# shangchi.net
KiCad netlist of a schematic drawn in EasyEDA Pro
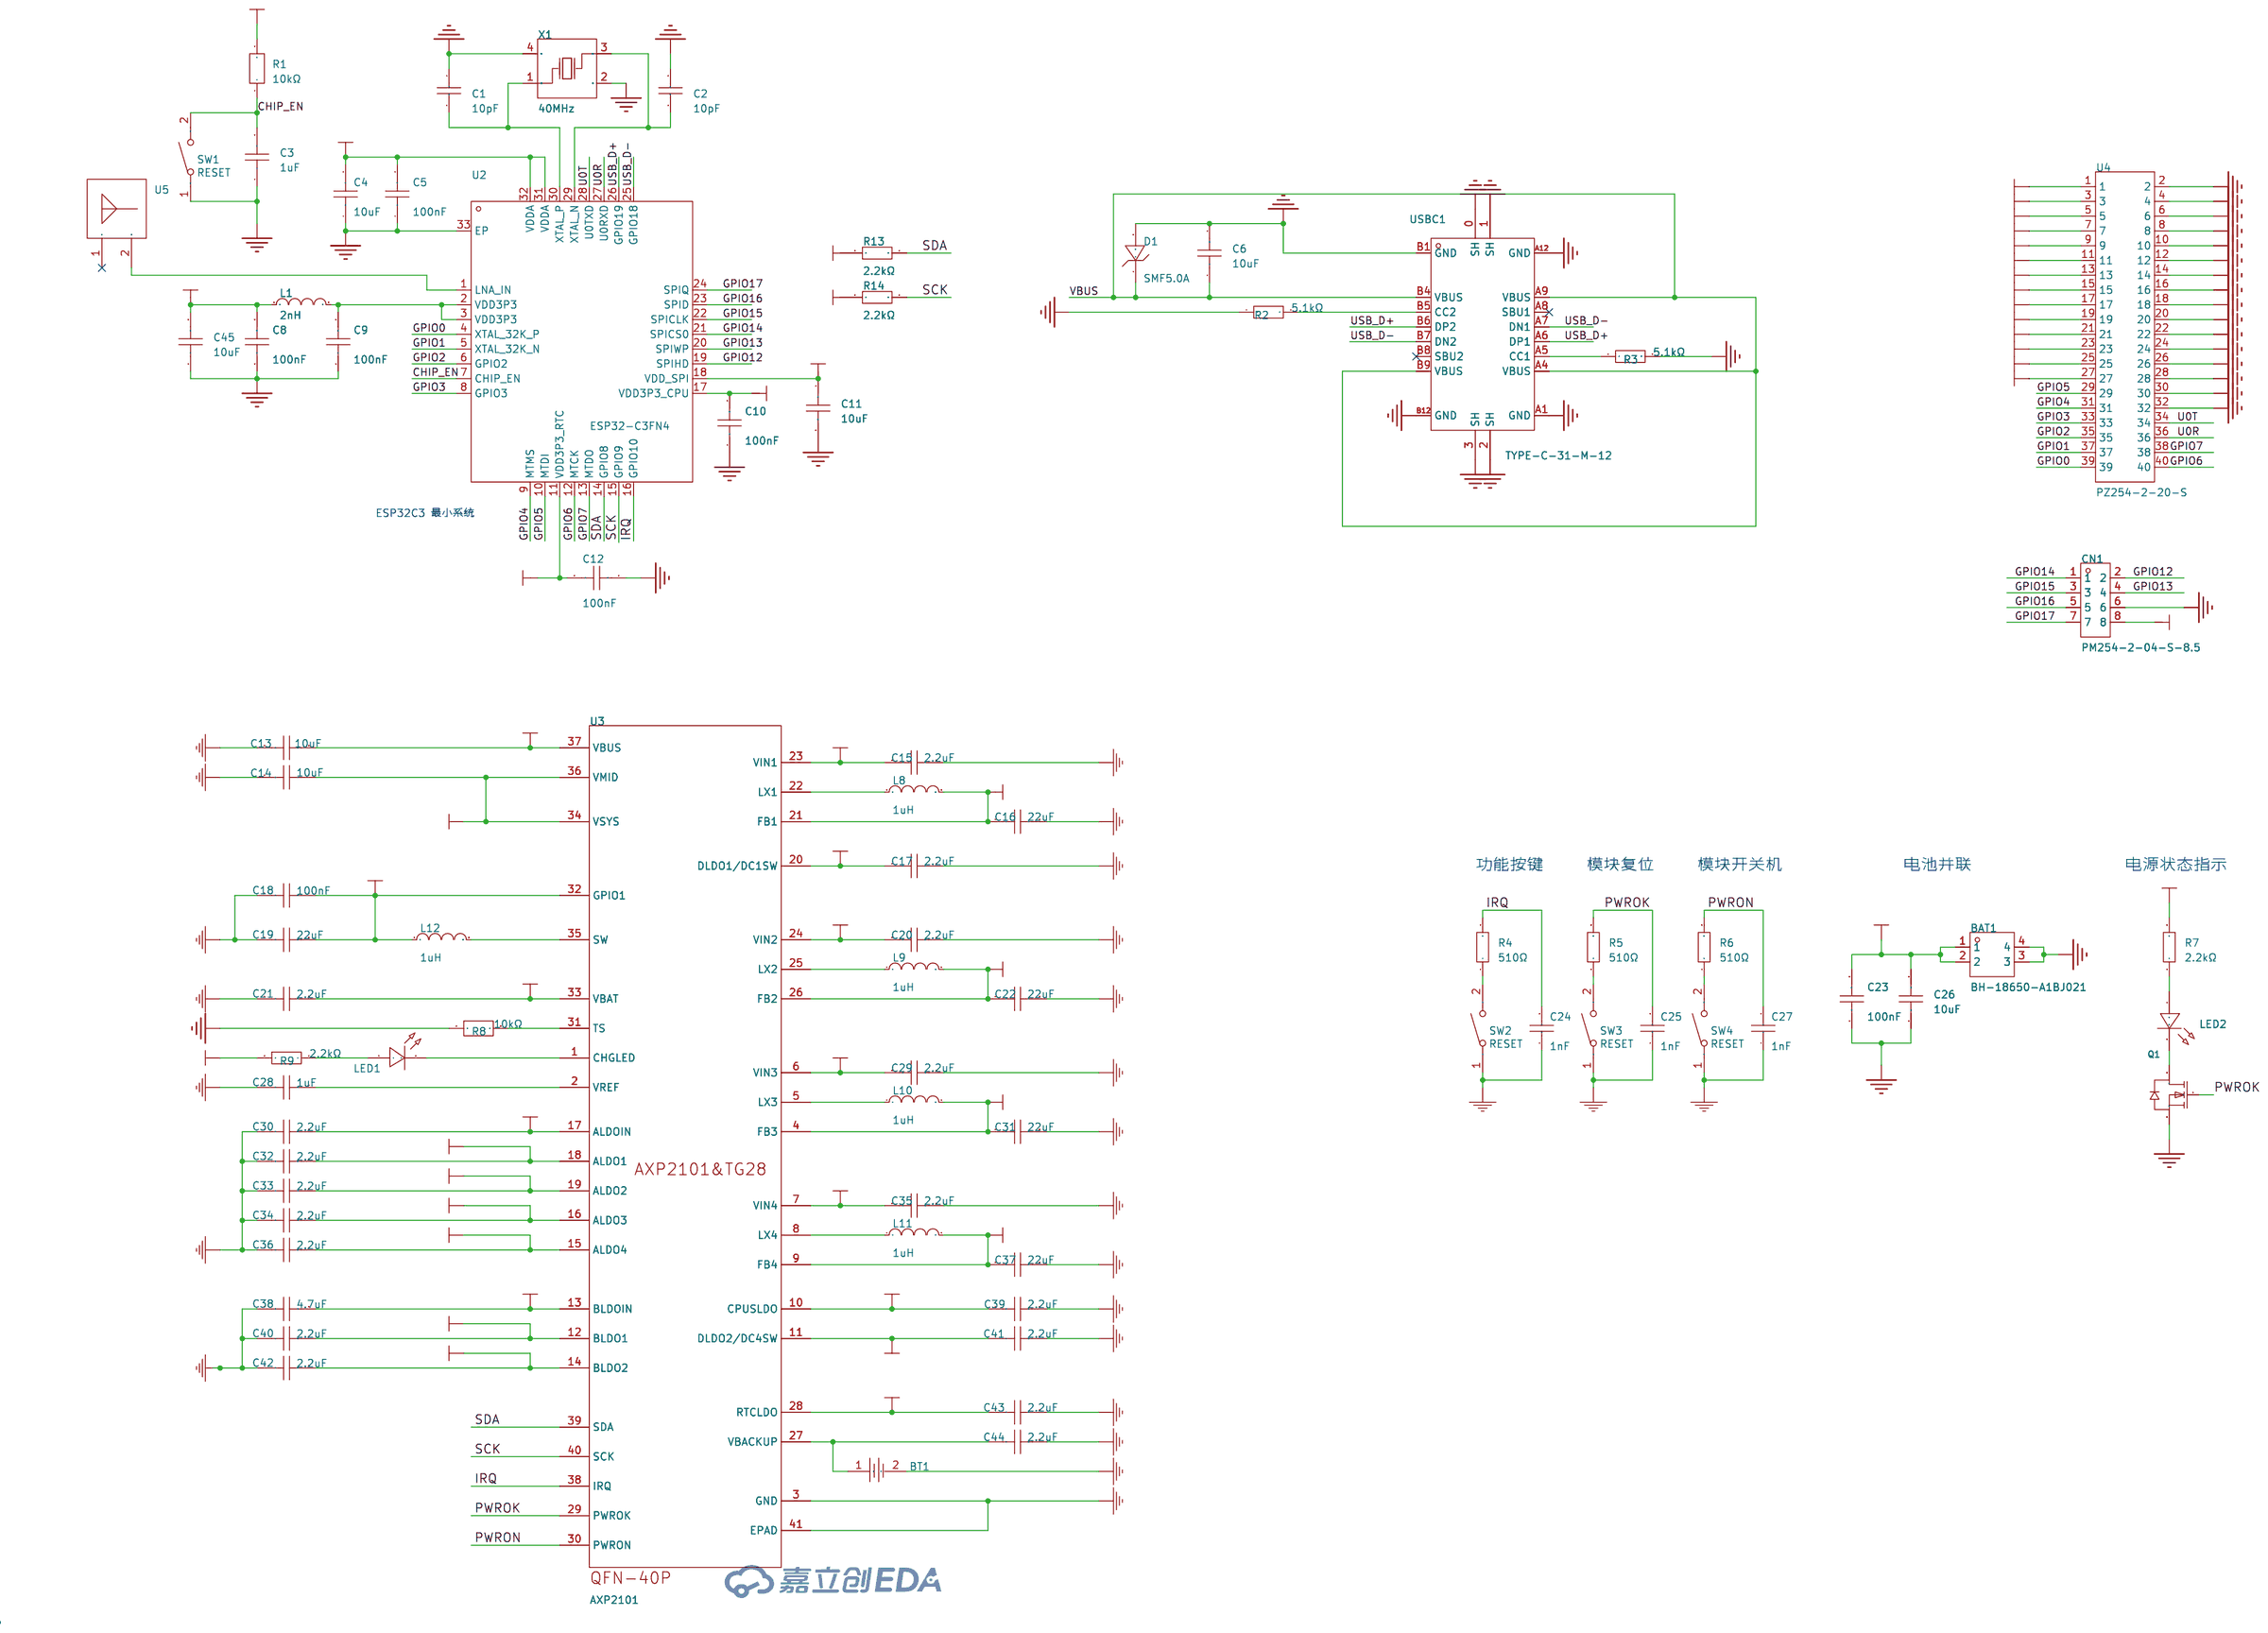
[diagram p0: schematic sheet]

(export (version "E")
  (design (tool "Eeschema 10.0.6"))
  (components
    (comp (ref "BAT1")
      (value "BH-18650-A1BJ021")
      (footprint "easyedapro:BAT-TH_L77.0-W39.9_BH-18650-A1BJ021")
      (description "连接器类型:电池盒;适用电池规格:-;触点电镀:镍;工作温度范围:-25°C~+85°C;")
      (fields (field (name "Manufacturer") "MYOUNG(美阳)"))
      (libsource (lib "easyedapro") (part "BH-18650-A1BJ021"))
    )
    (comp (ref "BT1")
      (value "CR1220-2ZX")
      (footprint "easyedapro:BAT-SMD_CR1220-2ZX")
      (fields (field (name "Manufacturer") "Q&J"))
      (libsource (lib "easyedapro") (part "CR1220-2ZX"))
    )
    (comp (ref "C1")
      (value "10pF")
      (footprint "easyedapro:C0603")
      (description "容值:10pF;精度:±5%;额定电压:50V;材质(温度系数):C0G;")
      (fields
        (field (name "Manufacturer Part") "CL10C100JB8NNNC")
        (field (name "Manufacturer") "SAMSUNG(三星)")
      )
      (libsource (lib "easyedapro") (part "CL10C100JB8NNNC"))
    )
    (comp (ref "C2")
      (value "10pF")
      (footprint "easyedapro:C0603")
      (description "容值:10pF;精度:±5%;额定电压:50V;材质(温度系数):C0G;")
      (fields
        (field (name "Manufacturer Part") "CL10C100JB8NNNC")
        (field (name "Manufacturer") "SAMSUNG(三星)")
      )
      (libsource (lib "easyedapro") (part "CL10C100JB8NNNC"))
    )
    (comp (ref "C3")
      (value "1uF")
      (fields (field (name "Manufacturer") "SAMSUNG(三星)"))
      (libsource (lib "easyedapro") (part "1uF/0603"))
    )
    (comp (ref "C4")
      (value "10uF")
      (footprint "easyedapro:C0603")
      (description "容值:10uF;精度:±10%;额定电压:10V;材质(温度系数):X5R;")
      (fields
        (field (name "Manufacturer Part") "CL10A106KP8NNNC")
        (field (name "Manufacturer") "SAMSUNG(三星)")
      )
      (libsource (lib "easyedapro") (part "CL10A106KP8NNNC"))
    )
    (comp (ref "C5")
      (value "100nF")
      (fields (field (name "Manufacturer") "SAMSUNG(三星)"))
      (libsource (lib "easyedapro") (part "100nF/0603"))
    )
    (comp (ref "C6")
      (value "10uF")
      (footprint "easyedapro:C0603")
      (description "容值:10uF;精度:±10%;额定电压:10V;材质(温度系数):X5R;")
      (fields
        (field (name "Manufacturer Part") "CL10A106KP8NNNC")
        (field (name "Manufacturer") "SAMSUNG(三星)")
      )
      (libsource (lib "easyedapro") (part "CL10A106KP8NNNC"))
    )
    (comp (ref "C8")
      (value "100nF")
      (fields (field (name "Manufacturer") "SAMSUNG(三星)"))
      (libsource (lib "easyedapro") (part "100nF/0603"))
    )
    (comp (ref "C9")
      (value "100nF")
      (fields (field (name "Manufacturer") "SAMSUNG(三星)"))
      (libsource (lib "easyedapro") (part "100nF/0603"))
    )
    (comp (ref "C10")
      (value "100nF")
      (fields (field (name "Manufacturer") "SAMSUNG(三星)"))
      (libsource (lib "easyedapro") (part "100nF/0603"))
    )
    (comp (ref "C11")
      (value "10uF")
      (fields (field (name "Manufacturer") "SAMSUNG(三星)"))
      (libsource (lib "easyedapro") (part "10uF/0603"))
    )
    (comp (ref "C12")
      (value "100nF")
      (fields (field (name "Manufacturer") "SAMSUNG(三星)"))
      (libsource (lib "easyedapro") (part "100nF/0603"))
    )
    (comp (ref "C13")
      (value "10uF")
      (footprint "easyedapro:C0603")
      (description "容值:10uF;精度:±10%;额定电压:10V;材质(温度系数):X5R;")
      (fields
        (field (name "Manufacturer Part") "CL10A106KP8NNNC")
        (field (name "Manufacturer") "SAMSUNG(三星)")
      )
      (libsource (lib "easyedapro") (part "CL10A106KP8NNNC"))
    )
    (comp (ref "C14")
      (value "10uF")
      (fields (field (name "Manufacturer") "SAMSUNG(三星)"))
      (libsource (lib "easyedapro") (part "10uF/0603"))
    )
    (comp (ref "C15")
      (value "2.2uF")
      (fields (field (name "Manufacturer") "SAMSUNG(三星)"))
      (libsource (lib "easyedapro") (part "2.2uF/0603"))
    )
    (comp (ref "C16")
      (value "22uF")
      (fields (field (name "Manufacturer") "SAMSUNG(三星)"))
      (libsource (lib "easyedapro") (part "22uF/0603"))
    )
    (comp (ref "C17")
      (value "2.2uF")
      (fields (field (name "Manufacturer") "SAMSUNG(三星)"))
      (libsource (lib "easyedapro") (part "2.2uF/0603"))
    )
    (comp (ref "C18")
      (value "100nF")
      (fields (field (name "Manufacturer") "SAMSUNG(三星)"))
      (libsource (lib "easyedapro") (part "100nF/0603"))
    )
    (comp (ref "C19")
      (value "22uF")
      (fields (field (name "Manufacturer") "SAMSUNG(三星)"))
      (libsource (lib "easyedapro") (part "22uF/0603"))
    )
    (comp (ref "C20")
      (value "2.2uF")
      (fields (field (name "Manufacturer") "SAMSUNG(三星)"))
      (libsource (lib "easyedapro") (part "2.2uF/0603"))
    )
    (comp (ref "C21")
      (value "2.2uF")
      (fields (field (name "Manufacturer") "SAMSUNG(三星)"))
      (libsource (lib "easyedapro") (part "2.2uF/0603"))
    )
    (comp (ref "C22")
      (value "22uF")
      (fields (field (name "Manufacturer") "SAMSUNG(三星)"))
      (libsource (lib "easyedapro") (part "22uF/0603"))
    )
    (comp (ref "C23")
      (value "100nF")
      (fields (field (name "Manufacturer") "SAMSUNG(三星)"))
      (libsource (lib "easyedapro") (part "100nF/0603"))
    )
    (comp (ref "C24")
      (value "1nF")
      (footprint "easyedapro:C0603")
      (description "容值:1nF;精度:±10%;额定电压:50V;材质(温度系数):X7R;")
      (fields
        (field (name "Manufacturer Part") "CL10B102KB8NNNC")
        (field (name "Manufacturer") "SAMSUNG(三星)")
      )
      (libsource (lib "easyedapro") (part "CL10B102KB8NNNC"))
    )
    (comp (ref "C25")
      (value "1nF")
      (footprint "easyedapro:C0603")
      (description "容值:1nF;精度:±10%;额定电压:50V;材质(温度系数):X7R;")
      (fields
        (field (name "Manufacturer Part") "CL10B102KB8NNNC")
        (field (name "Manufacturer") "SAMSUNG(三星)")
      )
      (libsource (lib "easyedapro") (part "CL10B102KB8NNNC"))
    )
    (comp (ref "C26")
      (value "10uF")
      (footprint "easyedapro:C0603")
      (description "容值:10uF;精度:±10%;额定电压:10V;材质(温度系数):X5R;")
      (fields
        (field (name "Manufacturer Part") "CL10A106KP8NNNC")
        (field (name "Manufacturer") "SAMSUNG(三星)")
      )
      (libsource (lib "easyedapro") (part "CL10A106KP8NNNC"))
    )
    (comp (ref "C27")
      (value "1nF")
      (footprint "easyedapro:C0603")
      (description "容值:1nF;精度:±10%;额定电压:50V;材质(温度系数):X7R;")
      (fields
        (field (name "Manufacturer Part") "CL10B102KB8NNNC")
        (field (name "Manufacturer") "SAMSUNG(三星)")
      )
      (libsource (lib "easyedapro") (part "CL10B102KB8NNNC"))
    )
    (comp (ref "C28")
      (value "1uF")
      (fields (field (name "Manufacturer") "SAMSUNG(三星)"))
      (libsource (lib "easyedapro") (part "1uF/0603"))
    )
    (comp (ref "C29")
      (value "2.2uF")
      (fields (field (name "Manufacturer") "SAMSUNG(三星)"))
      (libsource (lib "easyedapro") (part "2.2uF/0603"))
    )
    (comp (ref "C30")
      (value "2.2uF")
      (fields (field (name "Manufacturer") "SAMSUNG(三星)"))
      (libsource (lib "easyedapro") (part "2.2uF/0603"))
    )
    (comp (ref "C31")
      (value "22uF")
      (fields (field (name "Manufacturer") "SAMSUNG(三星)"))
      (libsource (lib "easyedapro") (part "22uF/0603"))
    )
    (comp (ref "C32")
      (value "2.2uF")
      (fields (field (name "Manufacturer") "SAMSUNG(三星)"))
      (libsource (lib "easyedapro") (part "2.2uF/0603"))
    )
    (comp (ref "C33")
      (value "2.2uF")
      (fields (field (name "Manufacturer") "SAMSUNG(三星)"))
      (libsource (lib "easyedapro") (part "2.2uF/0603"))
    )
    (comp (ref "C34")
      (value "2.2uF")
      (fields (field (name "Manufacturer") "SAMSUNG(三星)"))
      (libsource (lib "easyedapro") (part "2.2uF/0603"))
    )
    (comp (ref "C35")
      (value "2.2uF")
      (fields (field (name "Manufacturer") "SAMSUNG(三星)"))
      (libsource (lib "easyedapro") (part "2.2uF/0603"))
    )
    (comp (ref "C36")
      (value "2.2uF")
      (fields (field (name "Manufacturer") "SAMSUNG(三星)"))
      (libsource (lib "easyedapro") (part "2.2uF/0603"))
    )
    (comp (ref "C37")
      (value "22uF")
      (fields (field (name "Manufacturer") "SAMSUNG(三星)"))
      (libsource (lib "easyedapro") (part "22uF/0603"))
    )
    (comp (ref "C38")
      (value "4.7uF")
      (fields (field (name "Manufacturer") "SAMSUNG(三星)"))
      (libsource (lib "easyedapro") (part "4.7uF/0603"))
    )
    (comp (ref "C39")
      (value "2.2uF")
      (fields (field (name "Manufacturer") "SAMSUNG(三星)"))
      (libsource (lib "easyedapro") (part "2.2uF/0603"))
    )
    (comp (ref "C40")
      (value "2.2uF")
      (fields (field (name "Manufacturer") "SAMSUNG(三星)"))
      (libsource (lib "easyedapro") (part "2.2uF/0603"))
    )
    (comp (ref "C41")
      (value "2.2uF")
      (fields (field (name "Manufacturer") "SAMSUNG(三星)"))
      (libsource (lib "easyedapro") (part "2.2uF/0603"))
    )
    (comp (ref "C42")
      (value "2.2uF")
      (fields (field (name "Manufacturer") "SAMSUNG(三星)"))
      (libsource (lib "easyedapro") (part "2.2uF/0603"))
    )
    (comp (ref "C43")
      (value "2.2uF")
      (fields (field (name "Manufacturer") "SAMSUNG(三星)"))
      (libsource (lib "easyedapro") (part "2.2uF/0603"))
    )
    (comp (ref "C44")
      (value "2.2uF")
      (fields (field (name "Manufacturer") "SAMSUNG(三星)"))
      (libsource (lib "easyedapro") (part "2.2uF/0603"))
    )
    (comp (ref "C45")
      (value "10uF")
      (footprint "easyedapro:C0603")
      (description "容值:10uF;精度:±10%;额定电压:10V;材质(温度系数):X5R;")
      (fields
        (field (name "Manufacturer Part") "CL10A106KP8NNNC")
        (field (name "Manufacturer") "SAMSUNG(三星)")
      )
      (libsource (lib "easyedapro") (part "CL10A106KP8NNNC"))
    )
    (comp (ref "CN1")
      (value "PM254-2-04-S-8.5")
      (footprint "easyedapro:HDR-SMD_8P-P2.54-V-F-R2-C4-S7.1")
      (fields (field (name "Manufacturer") "HCTL(华灿天禄)"))
      (libsource (lib "easyedapro") (part "PM254-2-04-S-8.5"))
    )
    (comp (ref "D1")
      (value "SMF5.0A")
      (footprint "easyedapro:SOD-123F_L2.8-W1.8-LS3.7-RD")
      (description "反向截止电压(Vrwm):5V;最大钳位电压:9.2V;峰值脉冲电流(Ipp)@10/1000us:21.7A;峰值脉冲功率(Ppp)@10/1000us:200W;击穿电压:6.4V;")
      (fields (field (name "Manufacturer") "Littelfuse(美国力特)"))
      (libsource (lib "easyedapro") (part "SMF5.0A_C151296"))
    )
    (comp (ref "L1")
      (value "2nH")
      (footprint "easyedapro:L0402")
      (libsource (lib "easyedapro") (part "SDCL1005C10NJTDFM01"))
    )
    (comp (ref "L8")
      (value "1uH")
      (footprint "easyedapro:L0806")
      (description "电感值:1uH;精度:±20%;额定电流:3.1A;")
      (fields
        (field (name "Manufacturer Part") "HEI201610K-1R0M-Q8DG")
        (field (name "Manufacturer") "Chilisin(奇力新)")
      )
      (libsource (lib "easyedapro") (part "HEI201610K-1R0M-Q8DG"))
    )
    (comp (ref "L9")
      (value "1uH")
      (footprint "easyedapro:L0806")
      (description "电感值:1uH;精度:±20%;额定电流:3.1A;")
      (fields
        (field (name "Manufacturer Part") "HEI201610K-1R0M-Q8DG")
        (field (name "Manufacturer") "Chilisin(奇力新)")
      )
      (libsource (lib "easyedapro") (part "HEI201610K-1R0M-Q8DG"))
    )
    (comp (ref "L10")
      (value "1uH")
      (footprint "easyedapro:L0806")
      (description "电感值:1uH;精度:±20%;额定电流:3.1A;")
      (fields
        (field (name "Manufacturer Part") "HEI201610K-1R0M-Q8DG")
        (field (name "Manufacturer") "Chilisin(奇力新)")
      )
      (libsource (lib "easyedapro") (part "HEI201610K-1R0M-Q8DG"))
    )
    (comp (ref "L11")
      (value "1uH")
      (footprint "easyedapro:L0806")
      (description "电感值:1uH;精度:±20%;额定电流:3.1A;")
      (fields
        (field (name "Manufacturer Part") "HEI201610K-1R0M-Q8DG")
        (field (name "Manufacturer") "Chilisin(奇力新)")
      )
      (libsource (lib "easyedapro") (part "HEI201610K-1R0M-Q8DG"))
    )
    (comp (ref "L12")
      (value "1uH")
      (footprint "easyedapro:L0806")
      (description "电感值:1uH;精度:±20%;额定电流:3.1A;")
      (fields
        (field (name "Manufacturer Part") "HEI201610K-1R0M-Q8DG")
        (field (name "Manufacturer") "Chilisin(奇力新)")
      )
      (libsource (lib "easyedapro") (part "HEI201610K-1R0M-Q8DG"))
    )
    (comp (ref "LED1")
      (value "SZYY0603R")
      (footprint "easyedapro:LED0603_RED")
      (fields
        (field (name "Manufacturer Part") "19-217/R6C-AL1M2VY/3T")
        (field (name "Manufacturer") "EVERLIGHT(台湾亿光)")
      )
      (libsource (lib "easyedapro") (part "CHARGE"))
    )
    (comp (ref "LED2")
      (value "SZYY0603R")
      (footprint "easyedapro:LED0603_RED")
      (fields
        (field (name "Manufacturer Part") "19-217/R6C-AL1M2VY/3T")
        (field (name "Manufacturer") "EVERLIGHT(台湾亿光)")
      )
      (libsource (lib "easyedapro") (part "PWROK"))
    )
    (comp (ref "Q1")
      (value "AO3400-HXY")
      (footprint "easyedapro:SOT-23_L2.9-W1.3-P1.90-LS2.4-BR")
      (description "类型:N沟道;漏源电压(Vdss):30V;连续漏极电流(Id):5.8A;功率(Pd):1.4W;导通电阻(RDS(on)@Vgs,Id):28mΩ@10V,5.8A;")
      (fields (field (name "Manufacturer") "HXY MOSFET(华轩阳电子)"))
      (libsource (lib "easyedapro") (part "AO3400_C4748804"))
    )
    (comp (ref "R1")
      (value "10kΩ")
      (footprint "easyedapro:R0603")
      (description "电阻类型:厚膜电阻;阻值:10kΩ;精度:±1%;功率:100mW;温度系数:±100ppm/°C;")
      (fields (field (name "Manufacturer Part") "RC1608F103CS") (field (name "Manufacturer") "SAMSUNG(三星)"))
      (libsource (lib "easyedapro") (part "RC1608F103CS"))
    )
    (comp (ref "R2")
      (value "5.1kΩ")
      (footprint "easyedapro:R0603")
      (description "电阻类型:厚膜电阻;阻值:5.1kΩ;精度:±1%;功率:100mW;最大工作电压:75V;温度系数:±100ppm/°C;")
      (fields
        (field (name "Manufacturer Part") "0603WAF5101T5E")
        (field (name "Manufacturer") "UNI-ROYAL(厚声)")
      )
      (libsource (lib "easyedapro") (part "0603WAF5101T5E"))
    )
    (comp (ref "R3")
      (value "5.1kΩ")
      (footprint "easyedapro:R0603")
      (description "电阻类型:厚膜电阻;阻值:5.1kΩ;精度:±1%;功率:100mW;最大工作电压:75V;温度系数:±100ppm/°C;")
      (fields
        (field (name "Manufacturer Part") "0603WAF5101T5E")
        (field (name "Manufacturer") "UNI-ROYAL(厚声)")
      )
      (libsource (lib "easyedapro") (part "0603WAF5101T5E"))
    )
    (comp (ref "R4")
      (value "510Ω")
      (footprint "easyedapro:R0603")
      (description "电阻类型:厚膜电阻;阻值:510Ω;精度:±1%;功率:100mW;最大工作电压:75V;温度系数:±100ppm/°C;")
      (fields
        (field (name "Manufacturer Part") "0603WAF5100T5E")
        (field (name "Manufacturer") "UNI-ROYAL(厚声)")
      )
      (libsource (lib "easyedapro") (part "0603WAF5100T5E"))
    )
    (comp (ref "R5")
      (value "510Ω")
      (footprint "easyedapro:R0603")
      (description "电阻类型:厚膜电阻;阻值:510Ω;精度:±1%;功率:100mW;最大工作电压:75V;温度系数:±100ppm/°C;")
      (fields
        (field (name "Manufacturer Part") "0603WAF5100T5E")
        (field (name "Manufacturer") "UNI-ROYAL(厚声)")
      )
      (libsource (lib "easyedapro") (part "0603WAF5100T5E"))
    )
    (comp (ref "R6")
      (value "510Ω")
      (footprint "easyedapro:R0603")
      (description "电阻类型:厚膜电阻;阻值:510Ω;精度:±1%;功率:100mW;最大工作电压:75V;温度系数:±100ppm/°C;")
      (fields
        (field (name "Manufacturer Part") "0603WAF5100T5E")
        (field (name "Manufacturer") "UNI-ROYAL(厚声)")
      )
      (libsource (lib "easyedapro") (part "0603WAF5100T5E"))
    )
    (comp (ref "R7")
      (value "2.2kΩ")
      (footprint "easyedapro:R0603")
      (description "电阻类型:厚膜电阻;阻值:2.2kΩ;精度:±1%;功率:100mW;最大工作电压:75V;温度系数:±100ppm/°C;")
      (fields
        (field (name "Manufacturer Part") "0603WAF2201T5E")
        (field (name "Manufacturer") "UNI-ROYAL(厚声)")
      )
      (libsource (lib "easyedapro") (part "0603WAF2201T5E"))
    )
    (comp (ref "R8")
      (value "10kΩ")
      (footprint "easyedapro:R0603")
      (description "电阻类型:厚膜电阻;阻值:10kΩ;精度:±1%;功率:100mW;温度系数:±100ppm/°C;")
      (fields (field (name "Manufacturer Part") "RC1608F103CS") (field (name "Manufacturer") "SAMSUNG(三星)"))
      (libsource (lib "easyedapro") (part "RC1608F103CS"))
    )
    (comp (ref "R9")
      (value "2.2kΩ")
      (footprint "easyedapro:R0603")
      (description "电阻类型:厚膜电阻;阻值:2.2kΩ;精度:±1%;功率:100mW;最大工作电压:75V;温度系数:±100ppm/°C;")
      (fields
        (field (name "Manufacturer Part") "0603WAF2201T5E")
        (field (name "Manufacturer") "UNI-ROYAL(厚声)")
      )
      (libsource (lib "easyedapro") (part "0603WAF2201T5E"))
    )
    (comp (ref "R13")
      (value "2.2kΩ")
      (footprint "easyedapro:R0603")
      (description "电阻类型:厚膜电阻;阻值:2.2kΩ;精度:±1%;功率:100mW;最大工作电压:75V;温度系数:±100ppm/°C;")
      (fields
        (field (name "Manufacturer Part") "0603WAF2201T5E")
        (field (name "Manufacturer") "UNI-ROYAL(厚声)")
      )
      (libsource (lib "easyedapro") (part "0603WAF2201T5E"))
    )
    (comp (ref "R14")
      (value "2.2kΩ")
      (footprint "easyedapro:R0603")
      (description "电阻类型:厚膜电阻;阻值:2.2kΩ;精度:±1%;功率:100mW;最大工作电压:75V;温度系数:±100ppm/°C;")
      (fields
        (field (name "Manufacturer Part") "0603WAF2201T5E")
        (field (name "Manufacturer") "UNI-ROYAL(厚声)")
      )
      (libsource (lib "easyedapro") (part "0603WAF2201T5E"))
    )
    (comp (ref "SW1")
      (value "RESET")
      (footprint "easyedapro:SW-SMD_L4.0-W2.9-LS5.0")
      (fields
        (field (name "Manufacturer Part") "TS-1185EC-C-D-B")
        (field (name "Manufacturer") "XKB Enterprise")
      )
      (libsource (lib "easyedapro") (part "RESET"))
    )
    (comp (ref "SW2")
      (value "RESET")
      (footprint "easyedapro:SW-SMD_L4.0-W2.9-LS5.0")
      (fields
        (field (name "Manufacturer Part") "TS-1185EC-C-D-B")
        (field (name "Manufacturer") "XKB Enterprise")
      )
      (libsource (lib "easyedapro") (part "RESET"))
    )
    (comp (ref "SW3")
      (value "RESET")
      (footprint "easyedapro:SW-SMD_L4.0-W2.9-LS5.0")
      (fields
        (field (name "Manufacturer Part") "TS-1185EC-C-D-B")
        (field (name "Manufacturer") "XKB Enterprise")
      )
      (libsource (lib "easyedapro") (part "RESET"))
    )
    (comp (ref "SW4")
      (value "RESET")
      (footprint "easyedapro:SW-SMD_L4.0-W2.9-LS5.0")
      (fields
        (field (name "Manufacturer Part") "TS-1185EC-C-D-B")
        (field (name "Manufacturer") "XKB Enterprise")
      )
      (libsource (lib "easyedapro") (part "RESET"))
    )
    (comp (ref "U2")
      (value "ESP32-C3FN4")
      (footprint "easyedapro:QFN-32_L5.0-W5.0-P0.50-BL-EP3.7")
      (fields (field (name "Manufacturer") "ESPRESSIF(乐鑫)"))
      (libsource (lib "easyedapro") (part "ESP32-C3FN4"))
    )
    (comp (ref "U3")
      (value "AXP2101")
      (footprint "easyedapro:QFN-40_L5.0-W5.0-P0.40-TL-EP3.4")
      (description "A PMU designed by Allwinner")
      (fields (field (name "Manufacturer") "x-powers"))
      (libsource (lib "easyedapro") (part "AXP2101&TG28"))
    )
    (comp (ref "U4")
      (value "PZ254-2-20-S")
      (footprint "easyedapro:HDR-SMD_40P-P2.54-V-M-R2-C20-S7.4")
      (fields (field (name "Manufacturer") "HCTL(华灿天禄)"))
      (libsource (lib "easyedapro") (part "PZ254-2-20-S"))
    )
    (comp (ref "U5")
      (value "ADWH002")
      (footprint "easyedapro:ANT-SMD_L5.0-W2.0_HM5B")
      (description "天线类型:-;中心频率:2.45GHz;带宽:100MHz;增益:0.67dBi;功率:3W;驻波比:2;")
      (fields (field (name "Manufacturer") "MyAntenna(摩天射频)"))
      (libsource (lib "easyedapro") (part "ADWH002"))
    )
    (comp (ref "USBC1")
      (value "TYPE-C-31-M-12")
      (footprint "easyedapro:USB-C_SMD-TYPE-C-31-M-12")
      (description "连接器类型:Type-C;标准:-;公母:母;安装方式:-;触点数量:16P;端口数量:1;额定电流 - 电源:5A;工作温度范围:-;")
      (fields (field (name "Manufacturer") "韩国韩荣"))
      (libsource (lib "easyedapro") (part "TYPE-C-31-M-12"))
    )
    (comp (ref "X1")
      (value "40MHz")
      (footprint "easyedapro:OSC-SMD_4P-L3.2-W2.5-BL_SIT8008BI")
      (description "频率:40MHz;频率公差:±10ppm;负载电容:15pF;")
      (fields (field (name "Manufacturer Part") "X322540MPB4SI") (field (name "Manufacturer") "YXC(扬兴晶振)"))
      (libsource (lib "easyedapro") (part "X322540MPB4SI"))
    )
  )
  (nets
    (net (code "1") (name "/CHIP_EN") (class "Default")
      (node (ref "C3") (pin "2") (pinfunction "2_2") (pintype "unspecified"))
      (node (ref "R1") (pin "1") (pinfunction "1_1") (pintype "unspecified"))
      (node (ref "SW1") (pin "2") (pinfunction "2_2") (pintype "unspecified"))
      (node (ref "U2") (pin "7") (pinfunction "CHIP_EN_7") (pintype "unspecified"))
    )
    (net (code "2") (name "/GPIO0") (class "Default")
      (node (ref "U2") (pin "4") (pinfunction "XTAL_32K_P_4") (pintype "unspecified"))
      (node (ref "U4") (pin "39") (pinfunction "39_39") (pintype "unspecified"))
    )
    (net (code "3") (name "/GPIO1") (class "Default")
      (node (ref "U2") (pin "5") (pinfunction "XTAL_32K_N_5") (pintype "unspecified"))
      (node (ref "U4") (pin "37") (pinfunction "37_37") (pintype "unspecified"))
    )
    (net (code "4") (name "/GPIO2") (class "Default")
      (node (ref "U2") (pin "6") (pinfunction "GPIO2_6") (pintype "unspecified"))
      (node (ref "U4") (pin "35") (pinfunction "35_35") (pintype "unspecified"))
    )
    (net (code "5") (name "/GPIO3") (class "Default")
      (node (ref "U2") (pin "8") (pinfunction "GPIO3_8") (pintype "unspecified"))
      (node (ref "U4") (pin "33") (pinfunction "33_33") (pintype "unspecified"))
    )
    (net (code "6") (name "/GPIO4") (class "Default")
      (node (ref "U2") (pin "9") (pinfunction "MTMS_9") (pintype "unspecified"))
      (node (ref "U4") (pin "31") (pinfunction "31_31") (pintype "unspecified"))
    )
    (net (code "7") (name "/GPIO5") (class "Default")
      (node (ref "U2") (pin "10") (pinfunction "MTDI_10") (pintype "unspecified"))
      (node (ref "U4") (pin "29") (pinfunction "29_29") (pintype "unspecified"))
    )
    (net (code "8") (name "/GPIO6") (class "Default")
      (node (ref "U2") (pin "12") (pinfunction "MTCK_12") (pintype "unspecified"))
      (node (ref "U4") (pin "40") (pinfunction "40_40") (pintype "unspecified"))
    )
    (net (code "9") (name "/GPIO7") (class "Default")
      (node (ref "U2") (pin "13") (pinfunction "MTDO_13") (pintype "unspecified"))
      (node (ref "U4") (pin "38") (pinfunction "38_38") (pintype "unspecified"))
    )
    (net (code "10") (name "/GPIO12") (class "Default")
      (node (ref "CN1") (pin "2") (pinfunction "2_2") (pintype "unspecified"))
      (node (ref "U2") (pin "19") (pinfunction "SPIHD_19") (pintype "unspecified"))
    )
    (net (code "11") (name "/GPIO13") (class "Default")
      (node (ref "CN1") (pin "4") (pinfunction "4_4") (pintype "unspecified"))
      (node (ref "U2") (pin "20") (pinfunction "SPIWP_20") (pintype "unspecified"))
    )
    (net (code "12") (name "/GPIO14") (class "Default")
      (node (ref "CN1") (pin "1") (pinfunction "1_1") (pintype "unspecified"))
      (node (ref "U2") (pin "21") (pinfunction "SPICS0_21") (pintype "unspecified"))
    )
    (net (code "13") (name "/GPIO15") (class "Default")
      (node (ref "CN1") (pin "3") (pinfunction "3_3") (pintype "unspecified"))
      (node (ref "U2") (pin "22") (pinfunction "SPICLK_22") (pintype "unspecified"))
    )
    (net (code "14") (name "/GPIO16") (class "Default")
      (node (ref "CN1") (pin "5") (pinfunction "5_5") (pintype "unspecified"))
      (node (ref "U2") (pin "23") (pinfunction "SPID_23") (pintype "unspecified"))
    )
    (net (code "15") (name "/GPIO17") (class "Default")
      (node (ref "CN1") (pin "7") (pinfunction "7_7") (pintype "unspecified"))
      (node (ref "U2") (pin "24") (pinfunction "SPIQ_24") (pintype "unspecified"))
    )
    (net (code "16") (name "/IRQ") (class "Default")
      (node (ref "C24") (pin "2") (pinfunction "2_2") (pintype "input"))
      (node (ref "R4") (pin "2") (pinfunction "2_2") (pintype "input"))
      (node (ref "U2") (pin "16") (pinfunction "GPIO10_16") (pintype "unspecified"))
      (node (ref "U3") (pin "38") (pinfunction "IRQ_38") (pintype "unspecified"))
    )
    (net (code "17") (name "/PWROK") (class "Default")
      (node (ref "C25") (pin "2") (pinfunction "2_2") (pintype "input"))
      (node (ref "Q1") (pin "1") (pinfunction "G_1") (pintype "unspecified"))
      (node (ref "R5") (pin "2") (pinfunction "2_2") (pintype "input"))
      (node (ref "U3") (pin "29") (pinfunction "PWROK_29") (pintype "unspecified"))
    )
    (net (code "18") (name "/PWRON") (class "Default")
      (node (ref "C27") (pin "2") (pinfunction "2_2") (pintype "input"))
      (node (ref "R6") (pin "2") (pinfunction "2_2") (pintype "input"))
      (node (ref "U3") (pin "30") (pinfunction "PWRON_30") (pintype "unspecified"))
    )
    (net (code "19") (name "/SCK") (class "Default")
      (node (ref "R14") (pin "1") (pinfunction "1_1") (pintype "input"))
      (node (ref "U2") (pin "15") (pinfunction "GPIO9_15") (pintype "unspecified"))
      (node (ref "U3") (pin "40") (pinfunction "SCK_40") (pintype "unspecified"))
    )
    (net (code "20") (name "/SDA") (class "Default")
      (node (ref "R13") (pin "1") (pinfunction "1_1") (pintype "input"))
      (node (ref "U2") (pin "14") (pinfunction "GPIO8_14") (pintype "unspecified"))
      (node (ref "U3") (pin "39") (pinfunction "SDA_39") (pintype "unspecified"))
    )
    (net (code "21") (name "/U0R") (class "Default")
      (node (ref "U2") (pin "27") (pinfunction "U0RXD_27") (pintype "unspecified"))
      (node (ref "U4") (pin "36") (pinfunction "36_36") (pintype "unspecified"))
    )
    (net (code "22") (name "/U0T") (class "Default")
      (node (ref "U2") (pin "28") (pinfunction "U0TXD_28") (pintype "unspecified"))
      (node (ref "U4") (pin "34") (pinfunction "34_34") (pintype "unspecified"))
    )
    (net (code "23") (name "/USB_D+") (class "Default")
      (node (ref "U2") (pin "26") (pinfunction "GPIO19_26") (pintype "unspecified"))
      (node (ref "USBC1") (pin "A6") (pinfunction "DP1_A6") (pintype "unspecified"))
      (node (ref "USBC1") (pin "B6") (pinfunction "DP2_B6") (pintype "unspecified"))
    )
    (net (code "24") (name "/USB_D-") (class "Default")
      (node (ref "U2") (pin "25") (pinfunction "GPIO18_25") (pintype "unspecified"))
      (node (ref "USBC1") (pin "A7") (pinfunction "DN1_A7") (pintype "unspecified"))
      (node (ref "USBC1") (pin "B7") (pinfunction "DN2_B7") (pintype "unspecified"))
    )
    (net (code "25") (name "3V3") (class "Default")
      (node (ref "C10") (pin "2") (pinfunction "2_2") (pintype "unspecified"))
      (node (ref "C11") (pin "1") (pinfunction "1_1") (pintype "unspecified"))
      (node (ref "C12") (pin "2") (pinfunction "2_2") (pintype "unspecified"))
      (node (ref "C16") (pin "1") (pinfunction "1_1") (pintype "unspecified"))
      (node (ref "C4") (pin "2") (pinfunction "2_2") (pintype "unspecified"))
      (node (ref "C45") (pin "2") (pinfunction "2_2") (pintype "unspecified"))
      (node (ref "C5") (pin "2") (pinfunction "2_2") (pintype "unspecified"))
      (node (ref "C8") (pin "2") (pinfunction "2_2") (pintype "unspecified"))
      (node (ref "CN1") (pin "8") (pinfunction "8_8") (pintype "unspecified"))
      (node (ref "L1") (pin "1") (pinfunction "1_1") (pintype "unspecified"))
      (node (ref "L8") (pin "2") (pinfunction "2_2") (pintype "unspecified"))
      (node (ref "R1") (pin "2") (pinfunction "2_2") (pintype "unspecified"))
      (node (ref "R13") (pin "2") (pinfunction "2_2") (pintype "input"))
      (node (ref "R14") (pin "2") (pinfunction "2_2") (pintype "input"))
      (node (ref "U2") (pin "11") (pinfunction "VDD3P3_RTC_11") (pintype "unspecified"))
      (node (ref "U2") (pin "17") (pinfunction "VDD3P3_CPU_17") (pintype "unspecified"))
      (node (ref "U2") (pin "18") (pinfunction "VDD_SPI_18") (pintype "unspecified"))
      (node (ref "U2") (pin "31") (pinfunction "VDDA_31") (pintype "unspecified"))
      (node (ref "U2") (pin "32") (pinfunction "VDDA_32") (pintype "unspecified"))
      (node (ref "U3") (pin "21") (pinfunction "FB1_21") (pintype "unspecified"))
    )
    (net (code "26") (name "ALDO1") (class "Default")
      (node (ref "C32") (pin "2") (pinfunction "2_2") (pintype "unspecified"))
      (node (ref "U3") (pin "18") (pinfunction "ALDO1_18") (pintype "unspecified"))
      (node (ref "U4") (pin "13") (pinfunction "13_13") (pintype "unspecified"))
    )
    (net (code "27") (name "ALDO2") (class "Default")
      (node (ref "C33") (pin "2") (pinfunction "2_2") (pintype "unspecified"))
      (node (ref "U3") (pin "19") (pinfunction "ALDO2_19") (pintype "unspecified"))
      (node (ref "U4") (pin "11") (pinfunction "11_11") (pintype "unspecified"))
    )
    (net (code "28") (name "ALDO3") (class "Default")
      (node (ref "C34") (pin "2") (pinfunction "2_2") (pintype "unspecified"))
      (node (ref "U3") (pin "16") (pinfunction "ALDO3_16") (pintype "unspecified"))
      (node (ref "U4") (pin "15") (pinfunction "15_15") (pintype "unspecified"))
    )
    (net (code "29") (name "ALDO4") (class "Default")
      (node (ref "C36") (pin "2") (pinfunction "2_2") (pintype "unspecified"))
      (node (ref "U3") (pin "15") (pinfunction "ALDO4_15") (pintype "unspecified"))
      (node (ref "U4") (pin "17") (pinfunction "17_17") (pintype "unspecified"))
    )
    (net (code "30") (name "BLDO1") (class "Default")
      (node (ref "C40") (pin "2") (pinfunction "2_2") (pintype "unspecified"))
      (node (ref "U3") (pin "12") (pinfunction "BLDO1_12") (pintype "unspecified"))
      (node (ref "U4") (pin "21") (pinfunction "21_21") (pintype "unspecified"))
    )
    (net (code "31") (name "BLDO2") (class "Default")
      (node (ref "C42") (pin "2") (pinfunction "2_2") (pintype "unspecified"))
      (node (ref "U3") (pin "14") (pinfunction "BLDO2_14") (pintype "unspecified"))
      (node (ref "U4") (pin "19") (pinfunction "19_19") (pintype "unspecified"))
    )
    (net (code "32") (name "CPUS_LDO") (class "Default")
      (node (ref "C39") (pin "1") (pinfunction "1_1") (pintype "unspecified"))
      (node (ref "U3") (pin "10") (pinfunction "CPUSLDO_10") (pintype "unspecified"))
      (node (ref "U4") (pin "25") (pinfunction "25_25") (pintype "unspecified"))
    )
    (net (code "33") (name "DC1SW") (class "Default")
      (node (ref "C17") (pin "1") (pinfunction "1_1") (pintype "unspecified"))
      (node (ref "U3") (pin "20") (pinfunction "DLDO1/DC1SW_20") (pintype "unspecified"))
      (node (ref "U4") (pin "9") (pinfunction "9_9") (pintype "unspecified"))
    )
    (net (code "34") (name "DC4SW") (class "Default")
      (node (ref "C41") (pin "1") (pinfunction "1_1") (pintype "unspecified"))
      (node (ref "U3") (pin "11") (pinfunction "DLDO2/DC4SW_11") (pintype "unspecified"))
      (node (ref "U4") (pin "23") (pinfunction "23_23") (pintype "unspecified"))
    )
    (net (code "35") (name "DCDC2") (class "Default")
      (node (ref "C22") (pin "1") (pinfunction "1_1") (pintype "unspecified"))
      (node (ref "L9") (pin "2") (pinfunction "2_2") (pintype "unspecified"))
      (node (ref "U3") (pin "26") (pinfunction "FB2_26") (pintype "unspecified"))
      (node (ref "U4") (pin "7") (pinfunction "7_7") (pintype "unspecified"))
    )
    (net (code "36") (name "DCDC3") (class "Default")
      (node (ref "C31") (pin "1") (pinfunction "1_1") (pintype "unspecified"))
      (node (ref "L10") (pin "2") (pinfunction "2_2") (pintype "unspecified"))
      (node (ref "U3") (pin "4") (pinfunction "FB3_4") (pintype "unspecified"))
      (node (ref "U4") (pin "1") (pinfunction "1_1") (pintype "unspecified"))
    )
    (net (code "37") (name "DCDC4") (class "Default")
      (node (ref "C37") (pin "1") (pinfunction "1_1") (pintype "unspecified"))
      (node (ref "L11") (pin "2") (pinfunction "2_2") (pintype "unspecified"))
      (node (ref "U3") (pin "9") (pinfunction "FB4_9") (pintype "unspecified"))
      (node (ref "U4") (pin "27") (pinfunction "27_27") (pintype "unspecified"))
    )
    (net (code "38") (name "DCDC5") (class "Default")
      (node (ref "C18") (pin "2") (pinfunction "2_2") (pintype "unspecified"))
      (node (ref "C19") (pin "2") (pinfunction "2_2") (pintype "unspecified"))
      (node (ref "L12") (pin "1") (pinfunction "1_1") (pintype "unspecified"))
      (node (ref "U3") (pin "32") (pinfunction "GPIO1_32") (pintype "unspecified"))
      (node (ref "U4") (pin "3") (pinfunction "3_3") (pintype "unspecified"))
    )
    (net (code "39") (name "GND") (class "Default")
      (node (ref "BAT1") (pin "3") (pinfunction "3_3") (pintype "unspecified"))
      (node (ref "BAT1") (pin "4") (pinfunction "4_4") (pintype "unspecified"))
      (node (ref "BT1") (pin "2") (pinfunction "2_2") (pintype "input"))
      (node (ref "C1") (pin "2") (pinfunction "2_2") (pintype "input"))
      (node (ref "C10") (pin "1") (pinfunction "1_1") (pintype "unspecified"))
      (node (ref "C11") (pin "2") (pinfunction "2_2") (pintype "unspecified"))
      (node (ref "C12") (pin "1") (pinfunction "1_1") (pintype "unspecified"))
      (node (ref "C13") (pin "1") (pinfunction "1_1") (pintype "unspecified"))
      (node (ref "C14") (pin "2") (pinfunction "2_2") (pintype "unspecified"))
      (node (ref "C15") (pin "2") (pinfunction "2_2") (pintype "unspecified"))
      (node (ref "C16") (pin "2") (pinfunction "2_2") (pintype "unspecified"))
      (node (ref "C17") (pin "2") (pinfunction "2_2") (pintype "unspecified"))
      (node (ref "C18") (pin "1") (pinfunction "1_1") (pintype "unspecified"))
      (node (ref "C19") (pin "1") (pinfunction "1_1") (pintype "unspecified"))
      (node (ref "C2") (pin "2") (pinfunction "2_2") (pintype "input"))
      (node (ref "C20") (pin "2") (pinfunction "2_2") (pintype "unspecified"))
      (node (ref "C21") (pin "1") (pinfunction "1_1") (pintype "unspecified"))
      (node (ref "C22") (pin "2") (pinfunction "2_2") (pintype "unspecified"))
      (node (ref "C23") (pin "1") (pinfunction "1_1") (pintype "unspecified"))
      (node (ref "C24") (pin "1") (pinfunction "1_1") (pintype "input"))
      (node (ref "C25") (pin "1") (pinfunction "1_1") (pintype "input"))
      (node (ref "C26") (pin "1") (pinfunction "1_1") (pintype "unspecified"))
      (node (ref "C27") (pin "1") (pinfunction "1_1") (pintype "input"))
      (node (ref "C28") (pin "1") (pinfunction "1_1") (pintype "unspecified"))
      (node (ref "C29") (pin "2") (pinfunction "2_2") (pintype "unspecified"))
      (node (ref "C3") (pin "1") (pinfunction "1_1") (pintype "unspecified"))
      (node (ref "C30") (pin "1") (pinfunction "1_1") (pintype "unspecified"))
      (node (ref "C31") (pin "2") (pinfunction "2_2") (pintype "unspecified"))
      (node (ref "C32") (pin "1") (pinfunction "1_1") (pintype "unspecified"))
      (node (ref "C33") (pin "1") (pinfunction "1_1") (pintype "unspecified"))
      (node (ref "C34") (pin "1") (pinfunction "1_1") (pintype "unspecified"))
      (node (ref "C35") (pin "2") (pinfunction "2_2") (pintype "unspecified"))
      (node (ref "C36") (pin "1") (pinfunction "1_1") (pintype "unspecified"))
      (node (ref "C37") (pin "2") (pinfunction "2_2") (pintype "unspecified"))
      (node (ref "C38") (pin "1") (pinfunction "1_1") (pintype "unspecified"))
      (node (ref "C39") (pin "2") (pinfunction "2_2") (pintype "unspecified"))
      (node (ref "C4") (pin "1") (pinfunction "1_1") (pintype "unspecified"))
      (node (ref "C40") (pin "1") (pinfunction "1_1") (pintype "unspecified"))
      (node (ref "C41") (pin "2") (pinfunction "2_2") (pintype "unspecified"))
      (node (ref "C42") (pin "1") (pinfunction "1_1") (pintype "unspecified"))
      (node (ref "C43") (pin "2") (pinfunction "2_2") (pintype "unspecified"))
      (node (ref "C44") (pin "2") (pinfunction "2_2") (pintype "unspecified"))
      (node (ref "C45") (pin "1") (pinfunction "1_1") (pintype "unspecified"))
      (node (ref "C5") (pin "1") (pinfunction "1_1") (pintype "unspecified"))
      (node (ref "C6") (pin "2") (pinfunction "2_2") (pintype "unspecified"))
      (node (ref "C8") (pin "1") (pinfunction "1_1") (pintype "unspecified"))
      (node (ref "C9") (pin "1") (pinfunction "1_1") (pintype "unspecified"))
      (node (ref "CN1") (pin "6") (pinfunction "6_6") (pintype "unspecified"))
      (node (ref "D1") (pin "2") (pinfunction "2_2") (pintype "unspecified"))
      (node (ref "Q1") (pin "2") (pinfunction "S_2") (pintype "unspecified"))
      (node (ref "R2") (pin "1") (pinfunction "1_1") (pintype "input"))
      (node (ref "R3") (pin "2") (pinfunction "2_2") (pintype "input"))
      (node (ref "R8") (pin "1") (pinfunction "1_1") (pintype "unspecified"))
      (node (ref "SW1") (pin "1") (pinfunction "1_1") (pintype "unspecified"))
      (node (ref "SW2") (pin "1") (pinfunction "1_1") (pintype "unspecified"))
      (node (ref "SW3") (pin "1") (pinfunction "1_1") (pintype "unspecified"))
      (node (ref "SW4") (pin "1") (pinfunction "1_1") (pintype "unspecified"))
      (node (ref "U2") (pin "33") (pinfunction "EP_33") (pintype "unspecified"))
      (node (ref "U3") (pin "3") (pinfunction "GND_3") (pintype "unspecified"))
      (node (ref "U3") (pin "41") (pinfunction "EPAD_41") (pintype "unspecified"))
      (node (ref "U4") (pin "10") (pinfunction "10_10") (pintype "unspecified"))
      (node (ref "U4") (pin "12") (pinfunction "12_12") (pintype "unspecified"))
      (node (ref "U4") (pin "14") (pinfunction "14_14") (pintype "unspecified"))
      (node (ref "U4") (pin "16") (pinfunction "16_16") (pintype "unspecified"))
      (node (ref "U4") (pin "18") (pinfunction "18_18") (pintype "unspecified"))
      (node (ref "U4") (pin "2") (pinfunction "2_2") (pintype "unspecified"))
      (node (ref "U4") (pin "20") (pinfunction "20_20") (pintype "unspecified"))
      (node (ref "U4") (pin "22") (pinfunction "22_22") (pintype "unspecified"))
      (node (ref "U4") (pin "24") (pinfunction "24_24") (pintype "unspecified"))
      (node (ref "U4") (pin "26") (pinfunction "26_26") (pintype "unspecified"))
      (node (ref "U4") (pin "28") (pinfunction "28_28") (pintype "unspecified"))
      (node (ref "U4") (pin "30") (pinfunction "30_30") (pintype "unspecified"))
      (node (ref "U4") (pin "32") (pinfunction "32_32") (pintype "unspecified"))
      (node (ref "U4") (pin "4") (pinfunction "4_4") (pintype "unspecified"))
      (node (ref "U4") (pin "6") (pinfunction "6_6") (pintype "unspecified"))
      (node (ref "U4") (pin "8") (pinfunction "8_8") (pintype "unspecified"))
      (node (ref "USBC1") (pin "0") (pinfunction "SH_0") (pintype "unspecified"))
      (node (ref "USBC1") (pin "1") (pinfunction "SH_1") (pintype "unspecified"))
      (node (ref "USBC1") (pin "2") (pinfunction "SH_2") (pintype "unspecified"))
      (node (ref "USBC1") (pin "3") (pinfunction "SH_3") (pintype "unspecified"))
      (node (ref "USBC1") (pin "A1") (pinfunction "GND_A1") (pintype "unspecified"))
      (node (ref "USBC1") (pin "A12") (pinfunction "GND_A12") (pintype "unspecified"))
      (node (ref "USBC1") (pin "B1") (pinfunction "GND_B1") (pintype "unspecified"))
      (node (ref "USBC1") (pin "B12") (pinfunction "GND_B12") (pintype "unspecified"))
      (node (ref "X1") (pin "2") (pinfunction "GND_2") (pintype "unspecified"))
      (node (ref "X1") (pin "4") (pinfunction "GND_4") (pintype "unspecified"))
    )
    (net (code "40") (name "Net-(C9-Pad2)") (class "Default")
      (node (ref "C9") (pin "2") (pinfunction "2_2") (pintype "unspecified"))
      (node (ref "L1") (pin "2") (pinfunction "2_2") (pintype "unspecified"))
      (node (ref "U2") (pin "2") (pinfunction "VDD3P3_2") (pintype "unspecified"))
      (node (ref "U2") (pin "3") (pinfunction "VDD3P3_3") (pintype "unspecified"))
    )
    (net (code "41") (name "Net-(LED1-Pad1)") (class "Default")
      (node (ref "LED1") (pin "1") (pinfunction "1_1") (pintype "unspecified"))
      (node (ref "R9") (pin "1") (pinfunction "1_1") (pintype "input"))
    )
    (net (code "42") (name "Net-(LED2-Pad1)") (class "Default")
      (node (ref "LED2") (pin "1") (pinfunction "1_1") (pintype "unspecified"))
      (node (ref "R7") (pin "1") (pinfunction "1_1") (pintype "input"))
    )
    (net (code "43") (name "Net-(Q1-D)") (class "Default")
      (node (ref "LED2") (pin "2") (pinfunction "2_2") (pintype "unspecified"))
      (node (ref "Q1") (pin "3") (pinfunction "D_3") (pintype "unspecified"))
    )
    (net (code "44") (name "Net-(R4-Pad1)") (class "Default")
      (node (ref "R4") (pin "1") (pinfunction "1_1") (pintype "input"))
      (node (ref "SW2") (pin "2") (pinfunction "2_2") (pintype "unspecified"))
    )
    (net (code "45") (name "Net-(R5-Pad1)") (class "Default")
      (node (ref "R5") (pin "1") (pinfunction "1_1") (pintype "input"))
      (node (ref "SW3") (pin "2") (pinfunction "2_2") (pintype "unspecified"))
    )
    (net (code "46") (name "Net-(R6-Pad1)") (class "Default")
      (node (ref "R6") (pin "1") (pinfunction "1_1") (pintype "input"))
      (node (ref "SW4") (pin "2") (pinfunction "2_2") (pintype "unspecified"))
    )
    (net (code "47") (name "Net-(U2-LNA_IN)") (class "Default")
      (node (ref "U2") (pin "1") (pinfunction "LNA_IN_1") (pintype "unspecified"))
      (node (ref "U5") (pin "2") (pinfunction "GND_2") (pintype "unspecified"))
    )
    (net (code "48") (name "Net-(U2-XTAL_N)") (class "Default")
      (node (ref "C2") (pin "1") (pinfunction "1_1") (pintype "input"))
      (node (ref "U2") (pin "29") (pinfunction "XTAL_N_29") (pintype "unspecified"))
      (node (ref "X1") (pin "3") (pinfunction "OSC2_3") (pintype "unspecified"))
    )
    (net (code "49") (name "Net-(U2-XTAL_P)") (class "Default")
      (node (ref "C1") (pin "1") (pinfunction "1_1") (pintype "input"))
      (node (ref "U2") (pin "30") (pinfunction "XTAL_P_30") (pintype "unspecified"))
      (node (ref "X1") (pin "1") (pinfunction "OSC1_1") (pintype "unspecified"))
    )
    (net (code "50") (name "Net-(U3-CHGLED)") (class "Default")
      (node (ref "LED1") (pin "2") (pinfunction "2_2") (pintype "unspecified"))
      (node (ref "U3") (pin "1") (pinfunction "CHGLED_1") (pintype "unspecified"))
    )
    (net (code "51") (name "Net-(U3-LX1)") (class "Default")
      (node (ref "L8") (pin "1") (pinfunction "1_1") (pintype "unspecified"))
      (node (ref "U3") (pin "22") (pinfunction "LX1_22") (pintype "unspecified"))
    )
    (net (code "52") (name "Net-(U3-LX2)") (class "Default")
      (node (ref "L9") (pin "1") (pinfunction "1_1") (pintype "unspecified"))
      (node (ref "U3") (pin "25") (pinfunction "LX2_25") (pintype "unspecified"))
    )
    (net (code "53") (name "Net-(U3-LX3)") (class "Default")
      (node (ref "L10") (pin "1") (pinfunction "1_1") (pintype "unspecified"))
      (node (ref "U3") (pin "5") (pinfunction "LX3_5") (pintype "unspecified"))
    )
    (net (code "54") (name "Net-(U3-LX4)") (class "Default")
      (node (ref "L11") (pin "1") (pinfunction "1_1") (pintype "unspecified"))
      (node (ref "U3") (pin "8") (pinfunction "LX4_8") (pintype "unspecified"))
    )
    (net (code "55") (name "Net-(U3-SW)") (class "Default")
      (node (ref "L12") (pin "2") (pinfunction "2_2") (pintype "unspecified"))
      (node (ref "U3") (pin "35") (pinfunction "SW_35") (pintype "unspecified"))
    )
    (net (code "56") (name "Net-(U3-TS)") (class "Default")
      (node (ref "R8") (pin "2") (pinfunction "2_2") (pintype "unspecified"))
      (node (ref "U3") (pin "31") (pinfunction "TS_31") (pintype "unspecified"))
    )
    (net (code "57") (name "Net-(U3-VBACKUP)") (class "Default")
      (node (ref "BT1") (pin "1") (pinfunction "1_1") (pintype "input"))
      (node (ref "C44") (pin "1") (pinfunction "1_1") (pintype "unspecified"))
      (node (ref "U3") (pin "27") (pinfunction "VBACKUP_27") (pintype "unspecified"))
    )
    (net (code "58") (name "Net-(U3-VREF)") (class "Default")
      (node (ref "C28") (pin "2") (pinfunction "2_2") (pintype "unspecified"))
      (node (ref "U3") (pin "2") (pinfunction "VREF_2") (pintype "unspecified"))
    )
    (net (code "59") (name "Net-(USBC1-CC1)") (class "Default")
      (node (ref "R3") (pin "1") (pinfunction "1_1") (pintype "input"))
      (node (ref "USBC1") (pin "A5") (pinfunction "CC1_A5") (pintype "unspecified"))
    )
    (net (code "60") (name "Net-(USBC1-CC2)") (class "Default")
      (node (ref "R2") (pin "2") (pinfunction "2_2") (pintype "input"))
      (node (ref "USBC1") (pin "B5") (pinfunction "CC2_B5") (pintype "unspecified"))
    )
    (net (code "61") (name "RTC_LDO") (class "Default")
      (node (ref "C43") (pin "1") (pinfunction "1_1") (pintype "unspecified"))
      (node (ref "U3") (pin "28") (pinfunction "RTCLDO_28") (pintype "unspecified"))
      (node (ref "U4") (pin "5") (pinfunction "5_5") (pintype "unspecified"))
    )
    (net (code "62") (name "VBAT") (class "Default")
      (node (ref "BAT1") (pin "1") (pinfunction "1_1") (pintype "unspecified"))
      (node (ref "BAT1") (pin "2") (pinfunction "2_2") (pintype "unspecified"))
      (node (ref "C21") (pin "2") (pinfunction "2_2") (pintype "unspecified"))
      (node (ref "C23") (pin "2") (pinfunction "2_2") (pintype "unspecified"))
      (node (ref "C26") (pin "2") (pinfunction "2_2") (pintype "unspecified"))
      (node (ref "U3") (pin "33") (pinfunction "VBAT_33") (pintype "unspecified"))
    )
    (net (code "63") (name "VBUS") (class "Default")
      (node (ref "C13") (pin "2") (pinfunction "2_2") (pintype "unspecified"))
      (node (ref "C6") (pin "1") (pinfunction "1_1") (pintype "unspecified"))
      (node (ref "D1") (pin "1") (pinfunction "1_1") (pintype "unspecified"))
      (node (ref "U3") (pin "37") (pinfunction "VBUS_37") (pintype "unspecified"))
      (node (ref "USBC1") (pin "A4") (pinfunction "VBUS_A4") (pintype "unspecified"))
      (node (ref "USBC1") (pin "A9") (pinfunction "VBUS_A9") (pintype "unspecified"))
      (node (ref "USBC1") (pin "B4") (pinfunction "VBUS_B4") (pintype "unspecified"))
      (node (ref "USBC1") (pin "B9") (pinfunction "VBUS_B9") (pintype "unspecified"))
    )
    (net (code "64") (name "VSYS") (class "Default")
      (node (ref "C14") (pin "1") (pinfunction "1_1") (pintype "unspecified"))
      (node (ref "C15") (pin "1") (pinfunction "1_1") (pintype "unspecified"))
      (node (ref "C20") (pin "1") (pinfunction "1_1") (pintype "unspecified"))
      (node (ref "C29") (pin "1") (pinfunction "1_1") (pintype "unspecified"))
      (node (ref "C30") (pin "2") (pinfunction "2_2") (pintype "unspecified"))
      (node (ref "C35") (pin "1") (pinfunction "1_1") (pintype "unspecified"))
      (node (ref "C38") (pin "2") (pinfunction "2_2") (pintype "unspecified"))
      (node (ref "R7") (pin "2") (pinfunction "2_2") (pintype "input"))
      (node (ref "R9") (pin "2") (pinfunction "2_2") (pintype "input"))
      (node (ref "U3") (pin "13") (pinfunction "BLDOIN_13") (pintype "unspecified"))
      (node (ref "U3") (pin "17") (pinfunction "ALDOIN_17") (pintype "unspecified"))
      (node (ref "U3") (pin "23") (pinfunction "VIN1_23") (pintype "unspecified"))
      (node (ref "U3") (pin "24") (pinfunction "VIN2_24") (pintype "unspecified"))
      (node (ref "U3") (pin "34") (pinfunction "VSYS_34") (pintype "unspecified"))
      (node (ref "U3") (pin "36") (pinfunction "VMID_36") (pintype "unspecified"))
      (node (ref "U3") (pin "6") (pinfunction "VIN3_6") (pintype "unspecified"))
      (node (ref "U3") (pin "7") (pinfunction "VIN4_7") (pintype "unspecified"))
    )
    (net (code "65") (name "unconnected-(U5-IN-Pad1)") (class "Default")
      (node (ref "U5") (pin "1") (pinfunction "IN_1") (pintype "unspecified+no_connect"))
    )
    (net (code "66") (name "unconnected-(USBC1-SBU1-PadA8)") (class "Default")
      (node (ref "USBC1") (pin "A8") (pinfunction "SBU1_A8") (pintype "unspecified+no_connect"))
    )
    (net (code "67") (name "unconnected-(USBC1-SBU2-PadB8)") (class "Default")
      (node (ref "USBC1") (pin "B8") (pinfunction "SBU2_B8") (pintype "unspecified+no_connect"))
    )
  )
)
